# OpticalSensor.net
KiCad netlist of a schematic drawn in Altium Designer
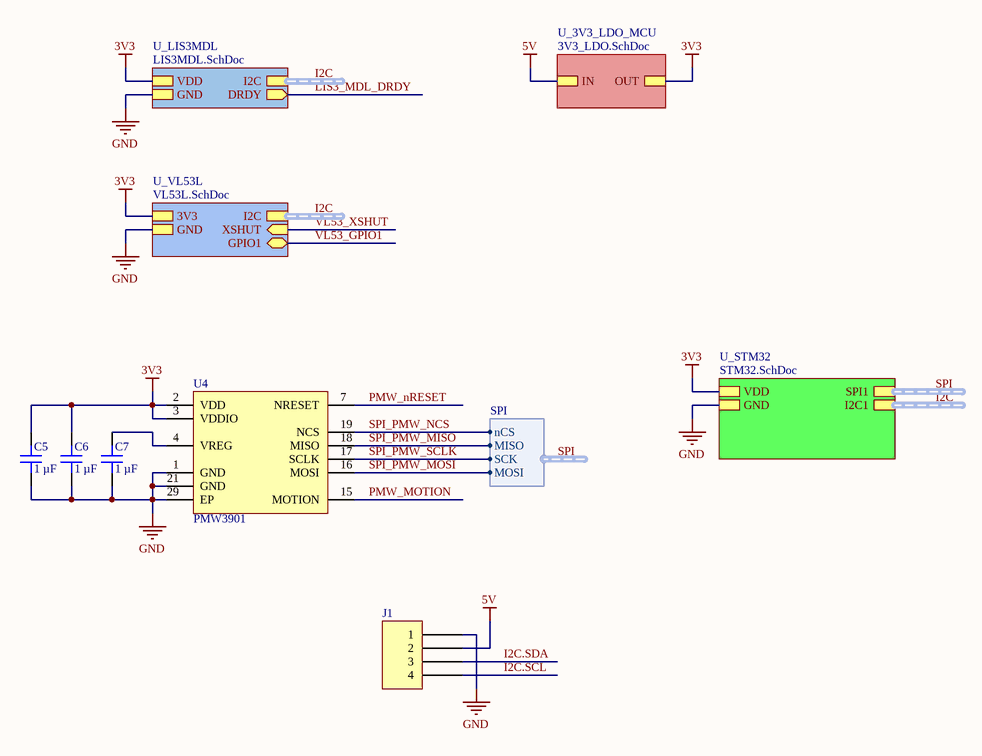
[diagram p0: OpticalSensor.SchDoc]

(export (version "E")
  (design (tool "Eeschema 10.0.6"))
  (components
    (comp (ref "C5")
      (value "1 µF")
      (footprint "CAP 0402_1005")
      (description "CAP CER 0.1UF 16V X7R 0402")
      (fields (field (name "PART NUMBER") "C0402C104K4RACAUTO") (field (name "MANUFACTURER") "KEMET"))
      (libsource (lib "Celestial Altium Library - altium_library") (part "Capacitor"))
    )
    (comp (ref "C6")
      (value "1 µF")
      (footprint "CAP 0402_1005")
      (description "CAP CER 0.1UF 16V X7R 0402")
      (fields (field (name "PART NUMBER") "C0402C104K4RACAUTO") (field (name "MANUFACTURER") "KEMET"))
      (libsource (lib "Celestial Altium Library - altium_library") (part "Capacitor"))
    )
    (comp (ref "C7")
      (value "1 µF")
      (footprint "CAP 0402_1005")
      (description "CAP CER 0.1UF 16V X7R 0402")
      (fields (field (name "PART NUMBER") "C0402C104K4RACAUTO") (field (name "MANUFACTURER") "KEMET"))
      (libsource (lib "Celestial Altium Library - altium_library") (part "Capacitor"))
    )
    (comp (ref "J1")
      (value "SM04B-SRSS-TB(LF)(SN)")
      (footprint "JST SM04B-SRSS-TB")
      (description "CONN HEADER SMD R/A 4POS 1MM")
      (fields (field (name "MANUFACTURER") "JST Sales America Inc."))
      (libsource (lib "Celestial Altium Library - altium_library") (part "4 Pin"))
    )
    (comp (ref "U4")
      (value "PMW3901")
      (footprint "PMW3901")
      (description "PMW3901. Optical Flow Sensor")
      (libsource (lib "IC") (part "PMW3901"))
    )
  )
  (nets
    (net (code "4") (name "/I2C.SCL") (class "Default")
      (node (ref "J1") (pin "4") (pinfunction "4_4") (pintype "passive"))
    )
    (net (code "5") (name "/I2C.SDA") (class "Default")
      (node (ref "J1") (pin "3") (pinfunction "3_3") (pintype "passive"))
    )
    (net (code "7") (name "/PMW_MOTION") (class "Default")
      (node (ref "U4") (pin "15") (pinfunction "MOTION_15") (pintype "passive"))
    )
    (net (code "8") (name "/PMW_nRESET") (class "Default")
      (node (ref "U4") (pin "7") (pinfunction "NRESET_7") (pintype "passive"))
    )
    (net (code "9") (name "/SPI_PMW_MISO") (class "Default")
      (node (ref "U4") (pin "18") (pinfunction "MISO_18") (pintype "passive"))
    )
    (net (code "10") (name "/SPI_PMW_MOSI") (class "Default")
      (node (ref "U4") (pin "16") (pinfunction "MOSI_16") (pintype "passive"))
    )
    (net (code "11") (name "/SPI_PMW_NCS") (class "Default")
      (node (ref "U4") (pin "19") (pinfunction "NCS_19") (pintype "passive"))
    )
    (net (code "12") (name "/SPI_PMW_SCLK") (class "Default")
      (node (ref "U4") (pin "17") (pinfunction "SCLK_17") (pintype "passive"))
    )
    (net (code "18") (name "3V3") (class "Default")
      (node (ref "C5") (pin "2") (pinfunction "2_2") (pintype "passive"))
      (node (ref "C6") (pin "2") (pinfunction "2_2") (pintype "passive"))
      (node (ref "U4") (pin "2") (pinfunction "VDD_2") (pintype "passive"))
      (node (ref "U4") (pin "3") (pinfunction "VDDIO_3") (pintype "passive"))
    )
    (net (code "19") (name "5V") (class "Default")
      (node (ref "J1") (pin "2") (pinfunction "2_2") (pintype "passive"))
    )
    (net (code "20") (name "GND") (class "Default")
      (node (ref "C5") (pin "1") (pinfunction "1_1") (pintype "passive"))
      (node (ref "C6") (pin "1") (pinfunction "1_1") (pintype "passive"))
      (node (ref "C7") (pin "1") (pinfunction "1_1") (pintype "passive"))
      (node (ref "J1") (pin "1") (pinfunction "1_1") (pintype "passive"))
      (node (ref "U4") (pin "1") (pinfunction "GND_1") (pintype "passive"))
      (node (ref "U4") (pin "21") (pinfunction "GND_21") (pintype "passive"))
      (node (ref "U4") (pin "29") (pinfunction "EP_29") (pintype "passive"))
    )
    (net (code "21") (name "Net-(U4-VREG)") (class "Default")
      (node (ref "C7") (pin "2") (pinfunction "2_2") (pintype "passive"))
      (node (ref "U4") (pin "4") (pinfunction "VREG_4") (pintype "passive"))
    )
  )
)
